# STM32-PROX_4.net
KiCad netlist of a schematic drawn in Altium Designer
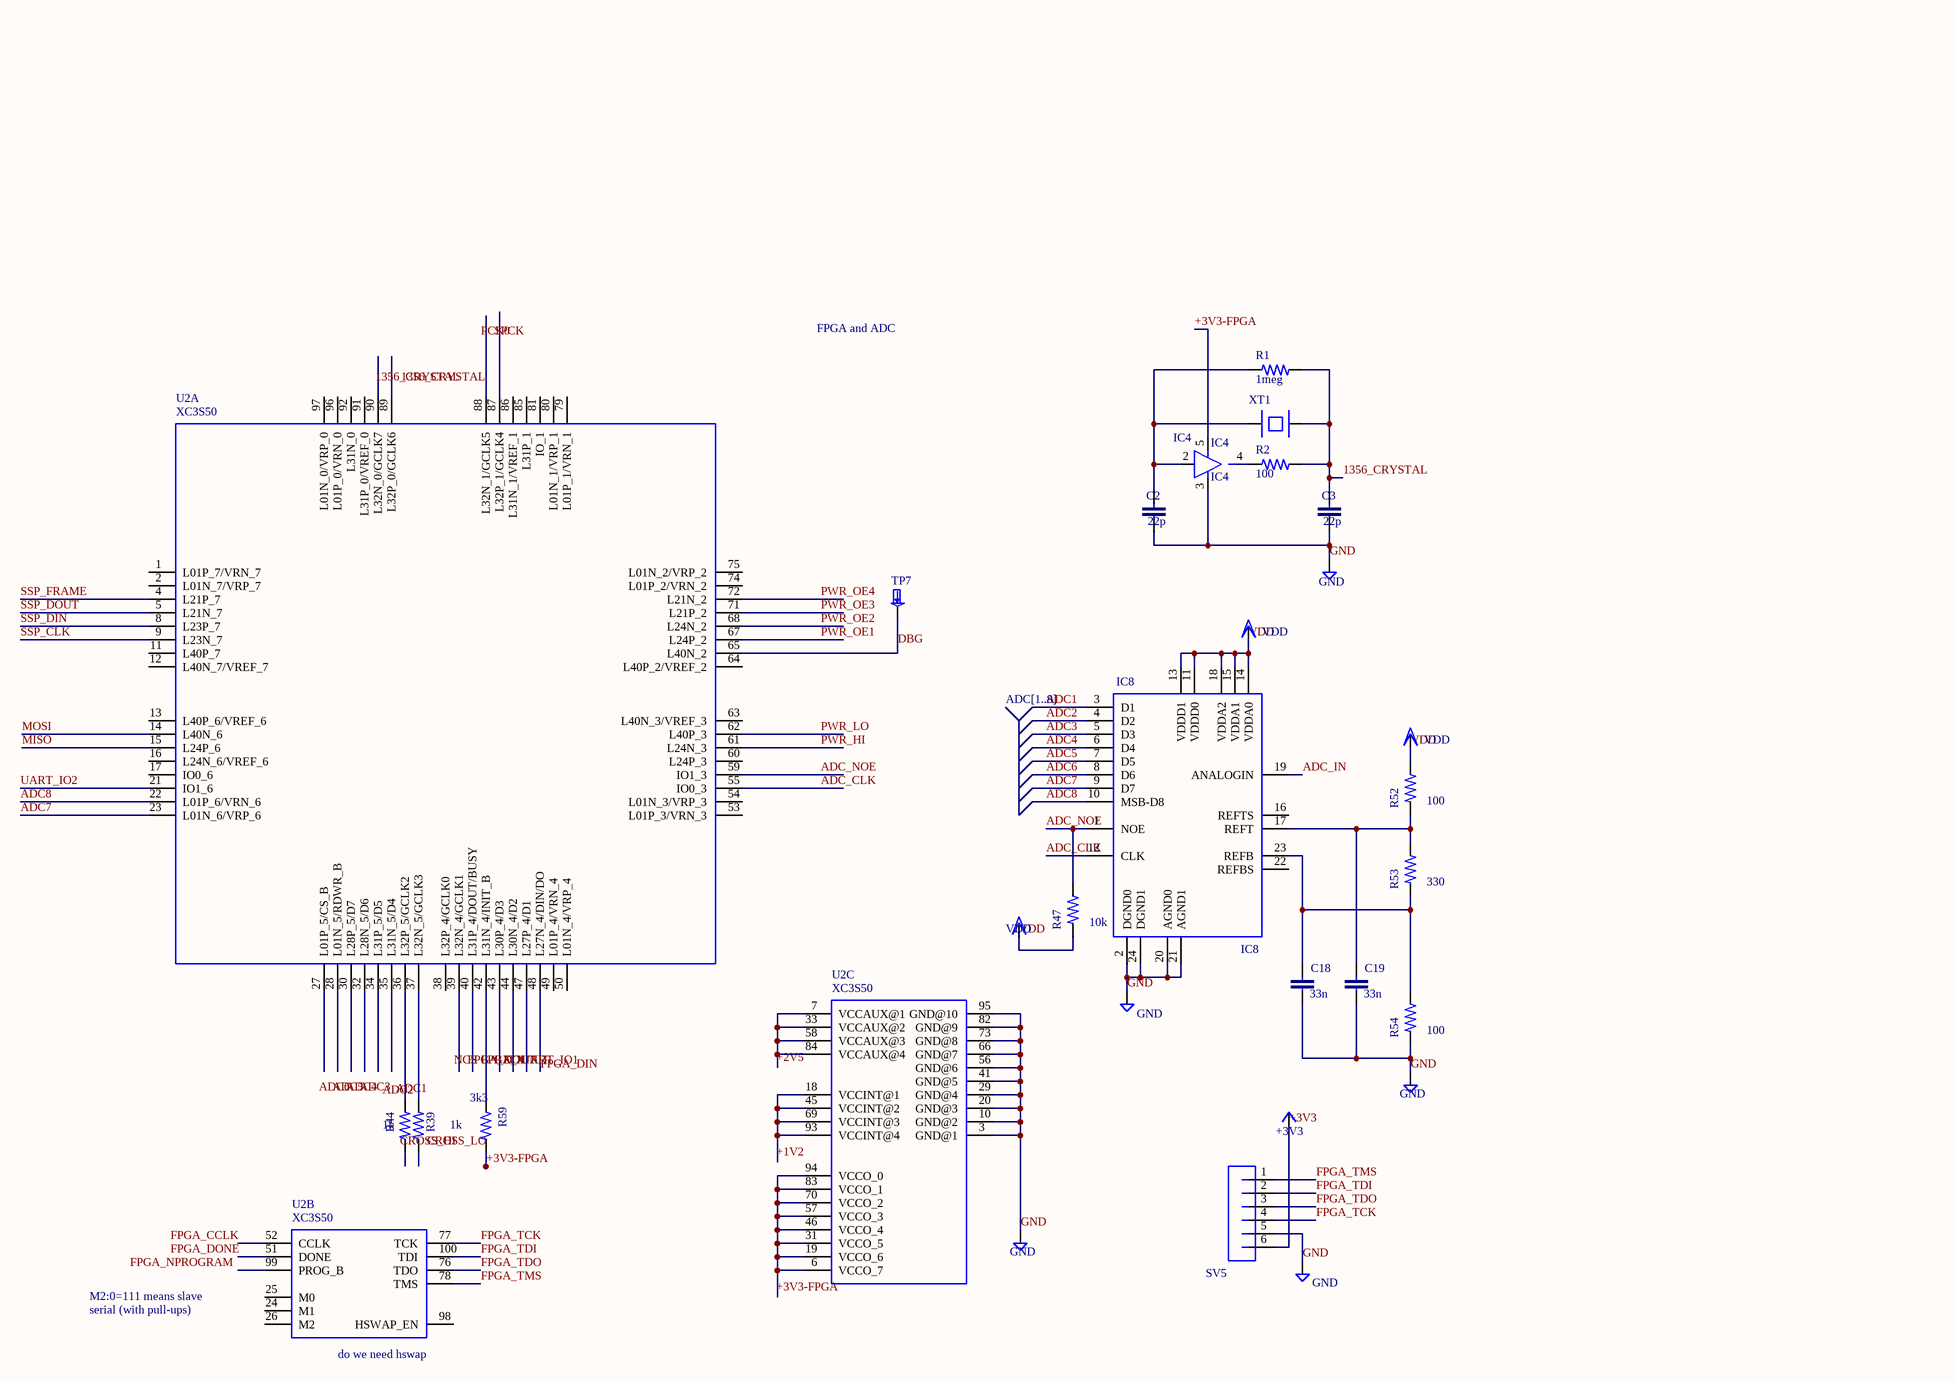
[diagram p0: STM32-PROX_4.SchDoc]

(export (version "E")
  (design (tool "Eeschema 10.0.6"))
  (components
    (comp (ref "C2")
      (value "22p")
      (footprint "RLC_0603")
      (libsource (lib "STM32-PROX") (part "CAPACITORRLC_0603"))
    )
    (comp (ref "C3")
      (value "22p")
      (footprint "RLC_0603")
      (libsource (lib "STM32-PROX") (part "CAPACITORRLC_0603"))
    )
    (comp (ref "C18") (value "33n") (footprint "RLC_0603") (libsource (lib "") (part "CAPACITORRLC_0603_1")))
    (comp (ref "C19") (value "33n") (footprint "RLC_0603") (libsource (lib "") (part "CAPACITORRLC_0603_1")))
    (comp (ref "IC4") (value "~") (footprint "SMV-5") (libsource (lib "STM32-PROX") (part "HCU-INVERTER")))
    (comp (ref "IC8") (value "~") (footprint "TSSOP-24") (libsource (lib "STM32-PROX") (part "TLC5540")))
    (comp (ref "R1")
      (value "1meg")
      (footprint "RLC_0603")
      (libsource (lib "STM32-PROX") (part "RESISTORRLC_0603"))
    )
    (comp (ref "R2")
      (value "100")
      (footprint "RLC_0603")
      (libsource (lib "STM32-PROX") (part "RESISTORRLC_0603"))
    )
    (comp (ref "R39") (value "1k") (footprint "RLC_0603") (libsource (lib "") (part "RESISTORRLC_0603_1")))
    (comp (ref "R44") (value "1k") (footprint "RLC_0603") (libsource (lib "") (part "RESISTORRLC_0603_1")))
    (comp (ref "R47")
      (value "10k")
      (footprint "RLC_0603")
      (libsource (lib "STM32-PROX") (part "RESISTORRLC_0603"))
    )
    (comp (ref "R52")
      (value "100")
      (footprint "RLC_0603")
      (libsource (lib "STM32-PROX") (part "RESISTORRLC_0603"))
    )
    (comp (ref "R53")
      (value "330")
      (footprint "RLC_0603")
      (libsource (lib "STM32-PROX") (part "RESISTORRLC_0603"))
    )
    (comp (ref "R54")
      (value "100")
      (footprint "RLC_0603")
      (libsource (lib "STM32-PROX") (part "RESISTORRLC_0603"))
    )
    (comp (ref "R59")
      (value "3k3")
      (footprint "RLC_0603")
      (libsource (lib "STM32-PROX") (part "RESISTORRLC_0603"))
    )
    (comp (ref "STM32-PROX") (value "GND") (libsource (lib "STM32-PROX") (part "GND")))
    (comp (ref "SV5")
      (value "~")
      (footprint "HEADER-MALE-6X1-0.100-UNKEYED")
      (libsource (lib "STM32-PROX") (part "HEADER-MALE-6X1"))
    )
    (comp (ref "TP7")
      (value "~")
      (footprint "KEYSTONE-SMD-TESTPOINT-5015")
      (libsource (lib "STM32-PROX") (part "TESTPADKEYSTONE-SMD"))
    )
    (comp (ref "U$5") (value "+3V3") (libsource (lib "STM32-PROX") (part "+3V3")))
    (comp (ref "U2") (value "XC3S50") (footprint "VQ100") (libsource (lib "") (part "XC3S50_2")))
    (comp (ref "V7") (value "GND") (libsource (lib "STM32-PROX") (part "GND")))
    (comp (ref "V24") (value "GND") (libsource (lib "STM32-PROX") (part "GND")))
    (comp (ref "V28") (value "GND") (libsource (lib "STM32-PROX") (part "GND")))
    (comp (ref "V55") (value "GND") (libsource (lib "STM32-PROX") (part "GND")))
    (comp (ref "VDD4") (value "VDD") (libsource (lib "STM32-PROX") (part "VDD")))
    (comp (ref "VDD10") (value "VDD") (libsource (lib "STM32-PROX") (part "VDD")))
    (comp (ref "VDD11") (value "VDD") (libsource (lib "STM32-PROX") (part "VDD")))
    (comp (ref "XT1")
      (value "~")
      (footprint "XTAL-SMD-CITIZEN-CS10")
      (libsource (lib "STM32-PROX") (part "XTAL-SMD-CITIZEN-CS10"))
    )
  )
  (nets
    (net (code "3") (name "/+3V3") (class "Default")
      (node (ref "SV5") (pin "6") (pinfunction "6_6") (pintype "passive"))
      (node (ref "U$5") (pin "0") (pinfunction "+3V3_0") (pintype "passive"))
    )
    (net (code "4") (name "/+3V3-FPGA") (class "Default")
      (node (ref "IC4") (pin "5") (pinfunction "VDD_5") (pintype "passive"))
      (node (ref "R59") (pin "2") (pinfunction "2_2") (pintype "passive"))
    )
    (net (code "5") (name "/1356_CRYSTAL") (class "Default")
      (node (ref "C3") (pin "1") (pinfunction "1_1") (pintype "passive"))
      (node (ref "R1") (pin "2") (pinfunction "2_2") (pintype "passive"))
      (node (ref "R2") (pin "2") (pinfunction "2_2") (pintype "passive"))
      (node (ref "XT1") (pin "B") (pinfunction "B_B") (pintype "passive"))
    )
    (net (code "6") (name "/ADC1") (class "Default")
      (node (ref "IC8") (pin "3") (pinfunction "D1_3") (pintype "passive"))
    )
    (net (code "7") (name "/ADC2") (class "Default")
      (node (ref "IC8") (pin "4") (pinfunction "D2_4") (pintype "passive"))
    )
    (net (code "8") (name "/ADC3") (class "Default")
      (node (ref "IC8") (pin "5") (pinfunction "D3_5") (pintype "passive"))
    )
    (net (code "9") (name "/ADC4") (class "Default")
      (node (ref "IC8") (pin "6") (pinfunction "D4_6") (pintype "passive"))
    )
    (net (code "10") (name "/ADC5") (class "Default")
      (node (ref "IC8") (pin "7") (pinfunction "D5_7") (pintype "passive"))
    )
    (net (code "11") (name "/ADC6") (class "Default")
      (node (ref "IC8") (pin "8") (pinfunction "D6_8") (pintype "passive"))
    )
    (net (code "12") (name "/ADC7") (class "Default")
      (node (ref "IC8") (pin "9") (pinfunction "D7_9") (pintype "passive"))
      (node (ref "U2") (pin "23") (pinfunction "L01N_6/VRP_6_23") (pintype "passive"))
    )
    (net (code "13") (name "/ADC8") (class "Default")
      (node (ref "IC8") (pin "10") (pinfunction "MSB-D8_10") (pintype "passive"))
      (node (ref "U2") (pin "22") (pinfunction "L01P_6/VRN_6_22") (pintype "passive"))
    )
    (net (code "14") (name "/ADC_CLK") (class "Default")
      (node (ref "IC8") (pin "12") (pinfunction "CLK_12") (pintype "passive"))
      (node (ref "U2") (pin "55") (pinfunction "IO0_3_55") (pintype "passive"))
    )
    (net (code "15") (name "/ADC_IN") (class "Default")
      (node (ref "IC8") (pin "19") (pinfunction "ANALOGIN_19") (pintype "passive"))
    )
    (net (code "16") (name "/ADC_NOE") (class "Default")
      (node (ref "IC8") (pin "1") (pinfunction "NOE_1") (pintype "passive"))
      (node (ref "R47") (pin "2") (pinfunction "2_2") (pintype "passive"))
      (node (ref "U2") (pin "59") (pinfunction "IO1_3_59") (pintype "passive"))
    )
    (net (code "19") (name "/DBG") (class "Default")
      (node (ref "TP7") (pin "1") (pinfunction "P$1_1") (pintype "passive"))
      (node (ref "U2") (pin "65") (pinfunction "L40N_2_65") (pintype "passive"))
    )
    (net (code "21") (name "/FPGA_DIN") (class "Default")
      (node (ref "U2") (pin "48") (pinfunction "L27N_4/DIN/DO_48") (pintype "passive"))
    )
    (net (code "26") (name "/FPGA_TCK") (class "Default")
      (node (ref "SV5") (pin "4") (pinfunction "4_4") (pintype "passive"))
      (node (ref "U2") (pin "77") (pinfunction "TCK_77") (pintype "passive"))
    )
    (net (code "27") (name "/FPGA_TDI") (class "Default")
      (node (ref "SV5") (pin "2") (pinfunction "2_2") (pintype "passive"))
      (node (ref "U2") (pin "100") (pinfunction "TDI_100") (pintype "passive"))
    )
    (net (code "28") (name "/FPGA_TDO") (class "Default")
      (node (ref "SV5") (pin "3") (pinfunction "3_3") (pintype "passive"))
      (node (ref "U2") (pin "76") (pinfunction "TDO_76") (pintype "passive"))
    )
    (net (code "29") (name "/FPGA_TMS") (class "Default")
      (node (ref "SV5") (pin "1") (pinfunction "1_1") (pintype "passive"))
      (node (ref "U2") (pin "78") (pinfunction "TMS_78") (pintype "passive"))
    )
    (net (code "30") (name "/GND") (class "Default")
      (node (ref "C18") (pin "2") (pinfunction "2_2") (pintype "passive"))
      (node (ref "C19") (pin "2") (pinfunction "2_2") (pintype "passive"))
      (node (ref "C2") (pin "2") (pinfunction "2_2") (pintype "passive"))
      (node (ref "C3") (pin "2") (pinfunction "2_2") (pintype "passive"))
      (node (ref "IC4") (pin "3") (pinfunction "VSS_3") (pintype "passive"))
      (node (ref "IC8") (pin "2") (pinfunction "DGND0_2") (pintype "passive"))
      (node (ref "IC8") (pin "20") (pinfunction "AGND0_20") (pintype "passive"))
      (node (ref "IC8") (pin "21") (pinfunction "AGND1_21") (pintype "passive"))
      (node (ref "IC8") (pin "24") (pinfunction "DGND1_24") (pintype "passive"))
      (node (ref "R54") (pin "1") (pinfunction "1_1") (pintype "passive"))
      (node (ref "STM32-PROX") (pin "0") (pinfunction "GND_0") (pintype "passive"))
      (node (ref "SV5") (pin "5") (pinfunction "5_5") (pintype "passive"))
      (node (ref "U2") (pin "10") (pinfunction "GND@2_10") (pintype "passive"))
      (node (ref "U2") (pin "20") (pinfunction "GND@3_20") (pintype "passive"))
      (node (ref "U2") (pin "29") (pinfunction "GND@4_29") (pintype "passive"))
      (node (ref "U2") (pin "3") (pinfunction "GND@1_3") (pintype "passive"))
      (node (ref "U2") (pin "41") (pinfunction "GND@5_41") (pintype "passive"))
      (node (ref "U2") (pin "56") (pinfunction "GND@6_56") (pintype "passive"))
      (node (ref "U2") (pin "66") (pinfunction "GND@7_66") (pintype "passive"))
      (node (ref "U2") (pin "73") (pinfunction "GND@8_73") (pintype "passive"))
      (node (ref "U2") (pin "82") (pinfunction "GND@9_82") (pintype "passive"))
      (node (ref "U2") (pin "95") (pinfunction "GND@10_95") (pintype "passive"))
      (node (ref "V24") (pin "0") (pinfunction "GND_0") (pintype "passive"))
      (node (ref "V28") (pin "0") (pinfunction "GND_0") (pintype "passive"))
      (node (ref "V55") (pin "0") (pinfunction "GND_0") (pintype "passive"))
      (node (ref "V7") (pin "0") (pinfunction "GND_0") (pintype "passive"))
    )
    (net (code "31") (name "/MISO") (class "Default")
      (node (ref "U2") (pin "15") (pinfunction "L24P_6_15") (pintype "passive"))
    )
    (net (code "32") (name "/MOSI") (class "Default")
      (node (ref "U2") (pin "14") (pinfunction "L40N_6_14") (pintype "passive"))
    )
    (net (code "35") (name "/PWR_HI") (class "Default")
      (node (ref "U2") (pin "61") (pinfunction "L24N_3_61") (pintype "passive"))
    )
    (net (code "36") (name "/PWR_LO") (class "Default")
      (node (ref "U2") (pin "62") (pinfunction "L40P_3_62") (pintype "passive"))
    )
    (net (code "37") (name "/PWR_OE1") (class "Default")
      (node (ref "U2") (pin "67") (pinfunction "L24P_2_67") (pintype "passive"))
    )
    (net (code "38") (name "/PWR_OE2") (class "Default")
      (node (ref "U2") (pin "68") (pinfunction "L24N_2_68") (pintype "passive"))
    )
    (net (code "39") (name "/PWR_OE3") (class "Default")
      (node (ref "U2") (pin "71") (pinfunction "L21P_2_71") (pintype "passive"))
    )
    (net (code "40") (name "/PWR_OE4") (class "Default")
      (node (ref "U2") (pin "72") (pinfunction "L21N_2_72") (pintype "passive"))
    )
    (net (code "43") (name "/SSP_CLK") (class "Default")
      (node (ref "U2") (pin "9") (pinfunction "L23N_7_9") (pintype "passive"))
    )
    (net (code "44") (name "/SSP_DIN") (class "Default")
      (node (ref "U2") (pin "8") (pinfunction "L23P_7_8") (pintype "passive"))
    )
    (net (code "45") (name "/SSP_DOUT") (class "Default")
      (node (ref "U2") (pin "5") (pinfunction "L21N_7_5") (pintype "passive"))
    )
    (net (code "46") (name "/SSP_FRAME") (class "Default")
      (node (ref "U2") (pin "4") (pinfunction "L21P_7_4") (pintype "passive"))
    )
    (net (code "49") (name "/UART_IO2") (class "Default")
      (node (ref "U2") (pin "21") (pinfunction "IO1_6_21") (pintype "passive"))
    )
    (net (code "50") (name "/VDD") (class "Default")
      (node (ref "IC8") (pin "11") (pinfunction "VDDD0_11") (pintype "passive"))
      (node (ref "IC8") (pin "13") (pinfunction "VDDD1_13") (pintype "passive"))
      (node (ref "IC8") (pin "14") (pinfunction "VDDA0_14") (pintype "passive"))
      (node (ref "IC8") (pin "15") (pinfunction "VDDA1_15") (pintype "passive"))
      (node (ref "IC8") (pin "18") (pinfunction "VDDA2_18") (pintype "passive"))
      (node (ref "R47") (pin "1") (pinfunction "1_1") (pintype "passive"))
      (node (ref "R52") (pin "2") (pinfunction "2_2") (pintype "passive"))
      (node (ref "VDD10") (pin "0") (pinfunction "VDD_0") (pintype "passive"))
      (node (ref "VDD11") (pin "0") (pinfunction "VDD_0") (pintype "passive"))
      (node (ref "VDD4") (pin "0") (pinfunction "VDD_0") (pintype "passive"))
    )
    (net (code "51") (name "Net-(IC4-A)") (class "Default")
      (node (ref "C2") (pin "1") (pinfunction "1_1") (pintype "passive"))
      (node (ref "IC4") (pin "2") (pinfunction "A_2") (pintype "passive"))
      (node (ref "R1") (pin "1") (pinfunction "1_1") (pintype "passive"))
      (node (ref "XT1") (pin "A") (pinfunction "A_A") (pintype "passive"))
    )
    (net (code "52") (name "Net-(IC4-Y)") (class "Default")
      (node (ref "IC4") (pin "4") (pinfunction "Y_4") (pintype "passive"))
      (node (ref "R2") (pin "1") (pinfunction "1_1") (pintype "passive"))
    )
    (net (code "53") (name "Net-(IC8-REFB)") (class "Default")
      (node (ref "C18") (pin "1") (pinfunction "1_1") (pintype "passive"))
      (node (ref "IC8") (pin "23") (pinfunction "REFB_23") (pintype "passive"))
      (node (ref "R53") (pin "1") (pinfunction "1_1") (pintype "passive"))
      (node (ref "R54") (pin "2") (pinfunction "2_2") (pintype "passive"))
    )
    (net (code "54") (name "Net-(IC8-REFT)") (class "Default")
      (node (ref "C19") (pin "1") (pinfunction "1_1") (pintype "passive"))
      (node (ref "IC8") (pin "17") (pinfunction "REFT_17") (pintype "passive"))
      (node (ref "R52") (pin "1") (pinfunction "1_1") (pintype "passive"))
      (node (ref "R53") (pin "2") (pinfunction "2_2") (pintype "passive"))
    )
    (net (code "55") (name "Net-(U2A-L31N_4{slash}INIT_B)") (class "Default")
      (node (ref "R59") (pin "1") (pinfunction "1_1") (pintype "passive"))
      (node (ref "U2") (pin "42") (pinfunction "L31N_4/INIT_B_42") (pintype "passive"))
    )
    (net (code "56") (name "Net-(U2A-L32N_5{slash}GCLK3)") (class "Default")
      (node (ref "R39") (pin "2") (pinfunction "2_2") (pintype "passive"))
      (node (ref "U2") (pin "37") (pinfunction "L32N_5/GCLK3_37") (pintype "passive"))
    )
    (net (code "57") (name "Net-(U2A-L32P_5{slash}GCLK2)") (class "Default")
      (node (ref "R44") (pin "2") (pinfunction "2_2") (pintype "passive"))
      (node (ref "U2") (pin "36") (pinfunction "L32P_5/GCLK2_36") (pintype "passive"))
    )
    (net (code "58") (name "Net-(U2C-VCCAUX@1)") (class "Default")
      (node (ref "U2") (pin "33") (pinfunction "VCCAUX@2_33") (pintype "passive"))
      (node (ref "U2") (pin "58") (pinfunction "VCCAUX@3_58") (pintype "passive"))
      (node (ref "U2") (pin "7") (pinfunction "VCCAUX@1_7") (pintype "passive"))
      (node (ref "U2") (pin "84") (pinfunction "VCCAUX@4_84") (pintype "passive"))
    )
    (net (code "59") (name "Net-(U2C-VCCINT@1)") (class "Default")
      (node (ref "U2") (pin "18") (pinfunction "VCCINT@1_18") (pintype "passive"))
      (node (ref "U2") (pin "45") (pinfunction "VCCINT@2_45") (pintype "passive"))
      (node (ref "U2") (pin "69") (pinfunction "VCCINT@3_69") (pintype "passive"))
      (node (ref "U2") (pin "93") (pinfunction "VCCINT@4_93") (pintype "passive"))
    )
    (net (code "60") (name "Net-(U2C-VCCO_0)") (class "Default")
      (node (ref "U2") (pin "19") (pinfunction "VCCO_6_19") (pintype "passive"))
      (node (ref "U2") (pin "31") (pinfunction "VCCO_5_31") (pintype "passive"))
      (node (ref "U2") (pin "46") (pinfunction "VCCO_4_46") (pintype "passive"))
      (node (ref "U2") (pin "57") (pinfunction "VCCO_3_57") (pintype "passive"))
      (node (ref "U2") (pin "6") (pinfunction "VCCO_7_6") (pintype "passive"))
      (node (ref "U2") (pin "70") (pinfunction "VCCO_2_70") (pintype "passive"))
      (node (ref "U2") (pin "83") (pinfunction "VCCO_1_83") (pintype "passive"))
      (node (ref "U2") (pin "94") (pinfunction "VCCO_0_94") (pintype "passive"))
    )
    (net (code "61") (name "unconnected-(IC8-REFBS-Pad22)") (class "Default")
      (node (ref "IC8") (pin "22") (pinfunction "REFBS_22") (pintype "passive"))
    )
    (net (code "62") (name "unconnected-(IC8-REFTS-Pad16)") (class "Default")
      (node (ref "IC8") (pin "16") (pinfunction "REFTS_16") (pintype "passive"))
    )
    (net (code "63") (name "unconnected-(R39-Pad1)") (class "Default")
      (node (ref "R39") (pin "1") (pinfunction "1_1") (pintype "passive"))
    )
    (net (code "64") (name "unconnected-(R44-Pad1)") (class "Default")
      (node (ref "R44") (pin "1") (pinfunction "1_1") (pintype "passive"))
    )
    (net (code "65") (name "unconnected-(U2A-IO0_6-Pad17)") (class "Default")
      (node (ref "U2") (pin "17") (pinfunction "IO0_6_17") (pintype "passive"))
    )
    (net (code "66") (name "unconnected-(U2A-IO_1-Pad81)") (class "Default")
      (node (ref "U2") (pin "81") (pinfunction "IO_1_81") (pintype "passive"))
    )
    (net (code "67") (name "unconnected-(U2A-L01N_0{slash}VRP_0-Pad97)") (class "Default")
      (node (ref "U2") (pin "97") (pinfunction "L01N_0/VRP_0_97") (pintype "passive"))
    )
    (net (code "68") (name "unconnected-(U2A-L01N_1{slash}VRP_1-Pad80)") (class "Default")
      (node (ref "U2") (pin "80") (pinfunction "L01N_1/VRP_1_80") (pintype "passive"))
    )
    (net (code "69") (name "unconnected-(U2A-L01N_2{slash}VRP_2-Pad75)") (class "Default")
      (node (ref "U2") (pin "75") (pinfunction "L01N_2/VRP_2_75") (pintype "passive"))
    )
    (net (code "70") (name "unconnected-(U2A-L01N_3{slash}VRP_3-Pad54)") (class "Default")
      (node (ref "U2") (pin "54") (pinfunction "L01N_3/VRP_3_54") (pintype "passive"))
    )
    (net (code "71") (name "unconnected-(U2A-L01N_4{slash}VRP_4-Pad50)") (class "Default")
      (node (ref "U2") (pin "50") (pinfunction "L01N_4/VRP_4_50") (pintype "passive"))
    )
    (net (code "72") (name "unconnected-(U2A-L01N_5{slash}RDWR_B-Pad28)") (class "Default")
      (node (ref "U2") (pin "28") (pinfunction "L01N_5/RDWR_B_28") (pintype "passive"))
    )
    (net (code "73") (name "unconnected-(U2A-L01N_7{slash}VRP_7-Pad2)") (class "Default")
      (node (ref "U2") (pin "2") (pinfunction "L01N_7/VRP_7_2") (pintype "passive"))
    )
    (net (code "74") (name "unconnected-(U2A-L01P_0{slash}VRN_0-Pad96)") (class "Default")
      (node (ref "U2") (pin "96") (pinfunction "L01P_0/VRN_0_96") (pintype "passive"))
    )
    (net (code "75") (name "unconnected-(U2A-L01P_1{slash}VRN_1-Pad79)") (class "Default")
      (node (ref "U2") (pin "79") (pinfunction "L01P_1/VRN_1_79") (pintype "passive"))
    )
    (net (code "76") (name "unconnected-(U2A-L01P_2{slash}VRN_2-Pad74)") (class "Default")
      (node (ref "U2") (pin "74") (pinfunction "L01P_2/VRN_2_74") (pintype "passive"))
    )
    (net (code "77") (name "unconnected-(U2A-L01P_3{slash}VRN_3-Pad53)") (class "Default")
      (node (ref "U2") (pin "53") (pinfunction "L01P_3/VRN_3_53") (pintype "passive"))
    )
    (net (code "78") (name "unconnected-(U2A-L01P_4{slash}VRN_4-Pad49)") (class "Default")
      (node (ref "U2") (pin "49") (pinfunction "L01P_4/VRN_4_49") (pintype "passive"))
    )
    (net (code "79") (name "unconnected-(U2A-L01P_5{slash}CS_B-Pad27)") (class "Default")
      (node (ref "U2") (pin "27") (pinfunction "L01P_5/CS_B_27") (pintype "passive"))
    )
    (net (code "80") (name "unconnected-(U2A-L01P_7{slash}VRN_7-Pad1)") (class "Default")
      (node (ref "U2") (pin "1") (pinfunction "L01P_7/VRN_7_1") (pintype "passive"))
    )
    (net (code "81") (name "unconnected-(U2A-L24N_6{slash}VREF_6-Pad16)") (class "Default")
      (node (ref "U2") (pin "16") (pinfunction "L24N_6/VREF_6_16") (pintype "passive"))
    )
    (net (code "82") (name "unconnected-(U2A-L24P_3-Pad60)") (class "Default")
      (node (ref "U2") (pin "60") (pinfunction "L24P_3_60") (pintype "passive"))
    )
    (net (code "83") (name "unconnected-(U2A-L27P_4{slash}D1-Pad47)") (class "Default")
      (node (ref "U2") (pin "47") (pinfunction "L27P_4/D1_47") (pintype "passive"))
    )
    (net (code "84") (name "unconnected-(U2A-L28N_5{slash}D6-Pad32)") (class "Default")
      (node (ref "U2") (pin "32") (pinfunction "L28N_5/D6_32") (pintype "passive"))
    )
    (net (code "85") (name "unconnected-(U2A-L28P_5{slash}D7-Pad30)") (class "Default")
      (node (ref "U2") (pin "30") (pinfunction "L28P_5/D7_30") (pintype "passive"))
    )
    (net (code "86") (name "unconnected-(U2A-L30N_4{slash}D2-Pad44)") (class "Default")
      (node (ref "U2") (pin "44") (pinfunction "L30N_4/D2_44") (pintype "passive"))
    )
    (net (code "87") (name "unconnected-(U2A-L30P_4{slash}D3-Pad43)") (class "Default")
      (node (ref "U2") (pin "43") (pinfunction "L30P_4/D3_43") (pintype "passive"))
    )
    (net (code "88") (name "unconnected-(U2A-L31N_0-Pad92)") (class "Default")
      (node (ref "U2") (pin "92") (pinfunction "L31N_0_92") (pintype "passive"))
    )
    (net (code "89") (name "unconnected-(U2A-L31N_1{slash}VREF_1-Pad86)") (class "Default")
      (node (ref "U2") (pin "86") (pinfunction "L31N_1/VREF_1_86") (pintype "passive"))
    )
    (net (code "90") (name "unconnected-(U2A-L31N_5{slash}D4-Pad35)") (class "Default")
      (node (ref "U2") (pin "35") (pinfunction "L31N_5/D4_35") (pintype "passive"))
    )
    (net (code "91") (name "unconnected-(U2A-L31P_0{slash}VREF_0-Pad91)") (class "Default")
      (node (ref "U2") (pin "91") (pinfunction "L31P_0/VREF_0_91") (pintype "passive"))
    )
    (net (code "92") (name "unconnected-(U2A-L31P_1-Pad85)") (class "Default")
      (node (ref "U2") (pin "85") (pinfunction "L31P_1_85") (pintype "passive"))
    )
    (net (code "93") (name "unconnected-(U2A-L31P_4{slash}DOUT{slash}BUSY-Pad40)") (class "Default")
      (node (ref "U2") (pin "40") (pinfunction "L31P_4/DOUT/BUSY_40") (pintype "passive"))
    )
    (net (code "94") (name "unconnected-(U2A-L31P_5{slash}D5-Pad34)") (class "Default")
      (node (ref "U2") (pin "34") (pinfunction "L31P_5/D5_34") (pintype "passive"))
    )
    (net (code "95") (name "unconnected-(U2A-L32N_0{slash}GCLK7-Pad90)") (class "Default")
      (node (ref "U2") (pin "90") (pinfunction "L32N_0/GCLK7_90") (pintype "passive"))
    )
    (net (code "96") (name "unconnected-(U2A-L32N_1{slash}GCLK5-Pad88)") (class "Default")
      (node (ref "U2") (pin "88") (pinfunction "L32N_1/GCLK5_88") (pintype "passive"))
    )
    (net (code "97") (name "unconnected-(U2A-L32N_4{slash}GCLK1-Pad39)") (class "Default")
      (node (ref "U2") (pin "39") (pinfunction "L32N_4/GCLK1_39") (pintype "passive"))
    )
    (net (code "98") (name "unconnected-(U2A-L32P_0{slash}GCLK6-Pad89)") (class "Default")
      (node (ref "U2") (pin "89") (pinfunction "L32P_0/GCLK6_89") (pintype "passive"))
    )
    (net (code "99") (name "unconnected-(U2A-L32P_1{slash}GCLK4-Pad87)") (class "Default")
      (node (ref "U2") (pin "87") (pinfunction "L32P_1/GCLK4_87") (pintype "passive"))
    )
    (net (code "100") (name "unconnected-(U2A-L32P_4{slash}GCLK0-Pad38)") (class "Default")
      (node (ref "U2") (pin "38") (pinfunction "L32P_4/GCLK0_38") (pintype "passive"))
    )
    (net (code "101") (name "unconnected-(U2A-L40N_3{slash}VREF_3-Pad63)") (class "Default")
      (node (ref "U2") (pin "63") (pinfunction "L40N_3/VREF_3_63") (pintype "passive"))
    )
    (net (code "102") (name "unconnected-(U2A-L40N_7{slash}VREF_7-Pad12)") (class "Default")
      (node (ref "U2") (pin "12") (pinfunction "L40N_7/VREF_7_12") (pintype "passive"))
    )
    (net (code "103") (name "unconnected-(U2A-L40P_2{slash}VREF_2-Pad64)") (class "Default")
      (node (ref "U2") (pin "64") (pinfunction "L40P_2/VREF_2_64") (pintype "passive"))
    )
    (net (code "104") (name "unconnected-(U2A-L40P_6{slash}VREF_6-Pad13)") (class "Default")
      (node (ref "U2") (pin "13") (pinfunction "L40P_6/VREF_6_13") (pintype "passive"))
    )
    (net (code "105") (name "unconnected-(U2A-L40P_7-Pad11)") (class "Default")
      (node (ref "U2") (pin "11") (pinfunction "L40P_7_11") (pintype "passive"))
    )
    (net (code "106") (name "unconnected-(U2B-CCLK-Pad52)") (class "Default")
      (node (ref "U2") (pin "52") (pinfunction "CCLK_52") (pintype "passive"))
    )
    (net (code "107") (name "unconnected-(U2B-DONE-Pad51)") (class "Default")
      (node (ref "U2") (pin "51") (pinfunction "DONE_51") (pintype "passive"))
    )
    (net (code "108") (name "unconnected-(U2B-HSWAP_EN-Pad98)") (class "Default")
      (node (ref "U2") (pin "98") (pinfunction "HSWAP_EN_98") (pintype "passive"))
    )
    (net (code "109") (name "unconnected-(U2B-M0-Pad25)") (class "Default")
      (node (ref "U2") (pin "25") (pinfunction "M0_25") (pintype "passive"))
    )
    (net (code "110") (name "unconnected-(U2B-M1-Pad24)") (class "Default")
      (node (ref "U2") (pin "24") (pinfunction "M1_24") (pintype "passive"))
    )
    (net (code "111") (name "unconnected-(U2B-M2-Pad26)") (class "Default")
      (node (ref "U2") (pin "26") (pinfunction "M2_26") (pintype "passive"))
    )
    (net (code "112") (name "unconnected-(U2B-PROG_B-Pad99)") (class "Default")
      (node (ref "U2") (pin "99") (pinfunction "PROG_B_99") (pintype "passive"))
    )
  )
)
